# Adafruit_USB_Isolator.net
KiCad netlist of a schematic drawn in EAGLE
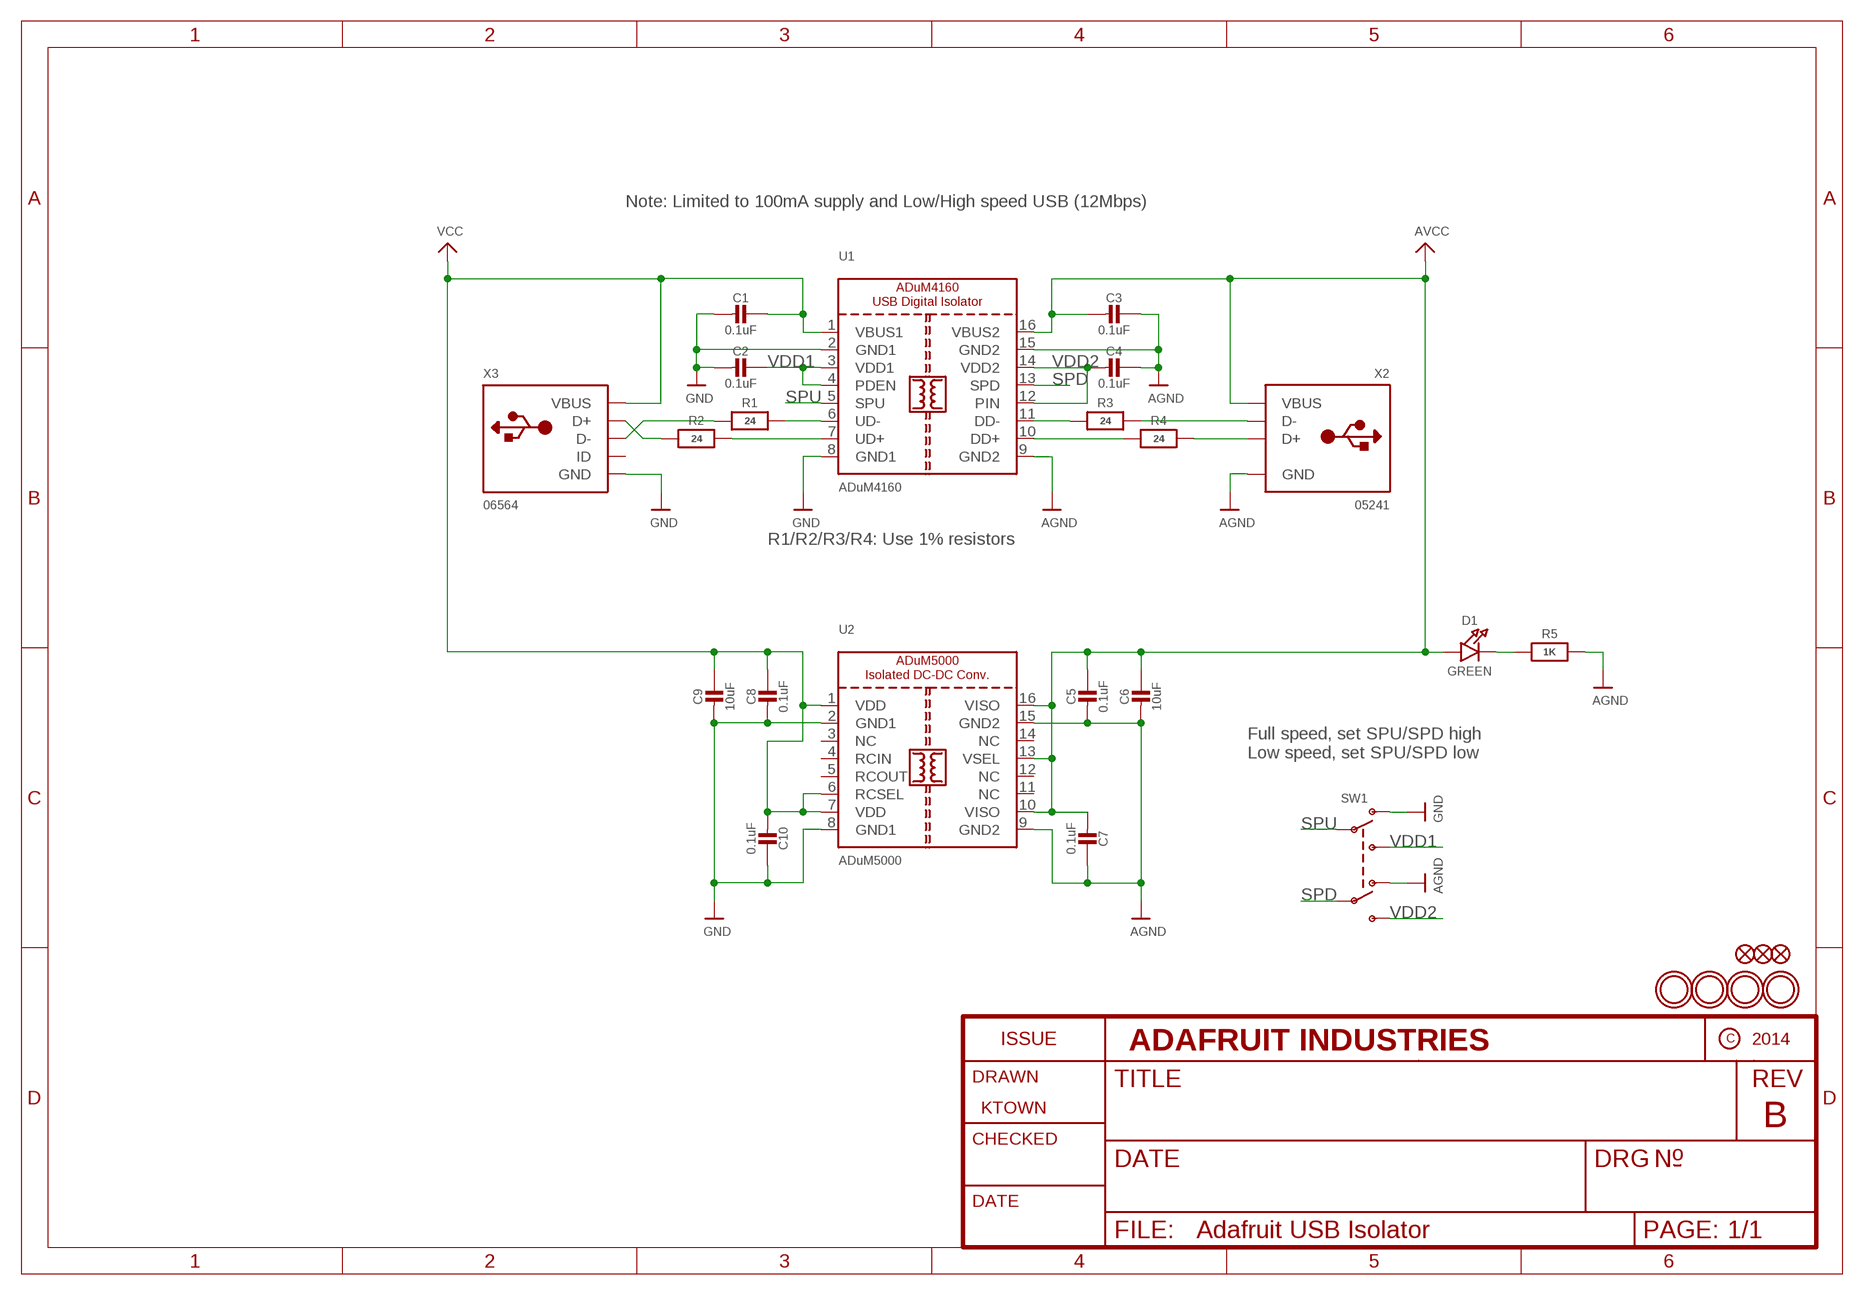
[diagram p0: schematic, sheet 1]

(export (version "E")
  (design (tool "Eeschema 10.0.6"))
  (components
    (comp (ref "C1")
      (value "0.1uF")
      (footprint "eagle-import:0805-NO")
      (libsource (lib "eagle-import") (part "CAP_CERAMIC0805-NOOUTLINE"))
    )
    (comp (ref "C2")
      (value "0.1uF")
      (footprint "eagle-import:0805-NO")
      (libsource (lib "eagle-import") (part "CAP_CERAMIC0805-NOOUTLINE"))
    )
    (comp (ref "C3")
      (value "0.1uF")
      (footprint "eagle-import:0805-NO")
      (libsource (lib "eagle-import") (part "CAP_CERAMIC0805-NOOUTLINE"))
    )
    (comp (ref "C4")
      (value "0.1uF")
      (footprint "eagle-import:0805-NO")
      (libsource (lib "eagle-import") (part "CAP_CERAMIC0805-NOOUTLINE"))
    )
    (comp (ref "C5")
      (value "0.1uF")
      (footprint "eagle-import:0805-NO")
      (libsource (lib "eagle-import") (part "CAP_CERAMIC0805-NOOUTLINE"))
    )
    (comp (ref "C6")
      (value "10uF")
      (footprint "eagle-import:0805-NO")
      (libsource (lib "eagle-import") (part "CAP_CERAMIC0805-NOOUTLINE"))
    )
    (comp (ref "C7")
      (value "0.1uF")
      (footprint "eagle-import:0805-NO")
      (libsource (lib "eagle-import") (part "CAP_CERAMIC0805-NOOUTLINE"))
    )
    (comp (ref "C8")
      (value "0.1uF")
      (footprint "eagle-import:0805-NO")
      (libsource (lib "eagle-import") (part "CAP_CERAMIC0805-NOOUTLINE"))
    )
    (comp (ref "C9")
      (value "10uF")
      (footprint "eagle-import:0805-NO")
      (libsource (lib "eagle-import") (part "CAP_CERAMIC0805-NOOUTLINE"))
    )
    (comp (ref "C10")
      (value "0.1uF")
      (footprint "eagle-import:0805-NO")
      (libsource (lib "eagle-import") (part "CAP_CERAMIC0805-NOOUTLINE"))
    )
    (comp (ref "D1")
      (value "GREEN")
      (footprint "eagle-import:CHIPLED_0805_NOOUTLINE")
      (libsource (lib "eagle-import") (part "LED0805_NOOUTLINE"))
    )
    (comp (ref "FID1")
      (value "FIDUCIAL\"\"")
      (footprint "eagle-import:FIDUCIAL_1MM")
      (libsource (lib "eagle-import") (part "FIDUCIAL{dblquote}{dblquote}"))
    )
    (comp (ref "FID2")
      (value "FIDUCIAL\"\"")
      (footprint "eagle-import:FIDUCIAL_1MM")
      (libsource (lib "eagle-import") (part "FIDUCIAL{dblquote}{dblquote}"))
    )
    (comp (ref "FID3")
      (value "FIDUCIAL\"\"")
      (footprint "eagle-import:FIDUCIAL_1MM")
      (libsource (lib "eagle-import") (part "FIDUCIAL{dblquote}{dblquote}"))
    )
    (comp (ref "R1")
      (value "24")
      (footprint "eagle-import:0805-NO")
      (libsource (lib "eagle-import") (part "RESISTOR0805_NOOUTLINE"))
    )
    (comp (ref "R2")
      (value "24")
      (footprint "eagle-import:0805-NO")
      (libsource (lib "eagle-import") (part "RESISTOR0805_NOOUTLINE"))
    )
    (comp (ref "R3")
      (value "24")
      (footprint "eagle-import:0805-NO")
      (libsource (lib "eagle-import") (part "RESISTOR0805_NOOUTLINE"))
    )
    (comp (ref "R4")
      (value "24")
      (footprint "eagle-import:_0805MP")
      (libsource (lib "eagle-import") (part "RESISTOR_0805MP"))
    )
    (comp (ref "R5")
      (value "1K")
      (footprint "eagle-import:0805-NO")
      (libsource (lib "eagle-import") (part "RESISTOR0805_NOOUTLINE"))
    )
    (comp (ref "SW1")
      (value "SWITCH_DPDTEG1390")
      (footprint "eagle-import:EG1390")
      (libsource (lib "eagle-import") (part "SWITCH_DPDTEG1390"))
    )
    (comp (ref "U$7")
      (value "MOUNTINGHOLE2.5_THICK")
      (footprint "eagle-import:MOUNTINGHOLE_2.5_PLATED_THICK")
      (libsource (lib "eagle-import") (part "MOUNTINGHOLE2.5_THICK"))
    )
    (comp (ref "U$8")
      (value "MOUNTINGHOLE2.5_THICK")
      (footprint "eagle-import:MOUNTINGHOLE_2.5_PLATED_THICK")
      (libsource (lib "eagle-import") (part "MOUNTINGHOLE2.5_THICK"))
    )
    (comp (ref "U$9")
      (value "MOUNTINGHOLE2.5_THICK")
      (footprint "eagle-import:MOUNTINGHOLE_2.5_PLATED_THICK")
      (libsource (lib "eagle-import") (part "MOUNTINGHOLE2.5_THICK"))
    )
    (comp (ref "U$10")
      (value "MOUNTINGHOLE2.5_THICK")
      (footprint "eagle-import:MOUNTINGHOLE_2.5_PLATED_THICK")
      (libsource (lib "eagle-import") (part "MOUNTINGHOLE2.5_THICK"))
    )
    (comp (ref "U1")
      (value "ADuM4160")
      (footprint "eagle-import:SOIC16WIDE")
      (libsource (lib "eagle-import") (part "ADUM4160"))
    )
    (comp (ref "U2")
      (value "ADuM5000")
      (footprint "eagle-import:SOIC16WIDE")
      (libsource (lib "eagle-import") (part "ADUM5000"))
    )
    (comp (ref "X2")
      (value "05241")
      (footprint "eagle-import:USB_HOST-PTH")
      (libsource (lib "eagle-import") (part "USB_TYPEAPTHFML"))
    )
    (comp (ref "X3")
      (value "06564")
      (footprint "eagle-import:USB-MINIB_LARGER")
      (libsource (lib "eagle-import") (part "USBMINIBLARGE"))
    )
  )
  (nets
    (net (code "1") (name "/SPD") (class "Default")
      (node (ref "SW1") (pin "P2") (pinfunction "P2_P2") (pintype "passive"))
      (node (ref "U1") (pin "13") (pinfunction "SPD_13") (pintype "input"))
    )
    (net (code "2") (name "/SPU") (class "Default")
      (node (ref "SW1") (pin "P1") (pinfunction "P1_P1") (pintype "passive"))
      (node (ref "U1") (pin "5") (pinfunction "SPU_5") (pintype "input"))
    )
    (net (code "3") (name "/VDD1") (class "Default")
      (node (ref "C2") (pin "1") (pinfunction "1_1") (pintype "passive"))
      (node (ref "SW1") (pin "S1") (pinfunction "S1_S1") (pintype "passive"))
      (node (ref "U1") (pin "3") (pinfunction "VDD1_3") (pintype "power_in"))
      (node (ref "U1") (pin "4") (pinfunction "PDEN_4") (pintype "input"))
    )
    (net (code "4") (name "/VDD2") (class "Default")
      (node (ref "C4") (pin "2") (pinfunction "2_2") (pintype "passive"))
      (node (ref "SW1") (pin "S2") (pinfunction "S2_S2") (pintype "passive"))
      (node (ref "U1") (pin "12") (pinfunction "PIN_12") (pintype "input"))
      (node (ref "U1") (pin "14") (pinfunction "VDD2_14") (pintype "power_in"))
    )
    (net (code "5") (name "AGND") (class "Default")
      (node (ref "C3") (pin "1") (pinfunction "1_1") (pintype "passive"))
      (node (ref "C4") (pin "1") (pinfunction "1_1") (pintype "passive"))
      (node (ref "C5") (pin "2") (pinfunction "2_2") (pintype "passive"))
      (node (ref "C6") (pin "2") (pinfunction "2_2") (pintype "passive"))
      (node (ref "C7") (pin "1") (pinfunction "1_1") (pintype "passive"))
      (node (ref "R5") (pin "2") (pinfunction "2_2") (pintype "passive"))
      (node (ref "SW1") (pin "O2") (pinfunction "O2_O2") (pintype "passive"))
      (node (ref "U1") (pin "15") (pinfunction "GND2_15") (pintype "power_in"))
      (node (ref "U1") (pin "9") (pinfunction "GND2_9") (pintype "power_in"))
      (node (ref "U2") (pin "15") (pinfunction "GND2_15") (pintype "power_in"))
      (node (ref "U2") (pin "9") (pinfunction "GND2_9") (pintype "power_in"))
      (node (ref "X2") (pin "GND") (pinfunction "GND_GND") (pintype "power_in"))
    )
    (net (code "6") (name "AVCC") (class "Default")
      (node (ref "C3") (pin "2") (pinfunction "2_2") (pintype "passive"))
      (node (ref "C5") (pin "1") (pinfunction "1_1") (pintype "passive"))
      (node (ref "C6") (pin "1") (pinfunction "1_1") (pintype "passive"))
      (node (ref "C7") (pin "2") (pinfunction "2_2") (pintype "passive"))
      (node (ref "D1") (pin "A") (pinfunction "A_A") (pintype "passive"))
      (node (ref "U1") (pin "16") (pinfunction "VBUS2_16") (pintype "power_in"))
      (node (ref "U2") (pin "10") (pinfunction "VISO_10") (pintype "bidirectional"))
      (node (ref "U2") (pin "13") (pinfunction "VSEL_13") (pintype "input"))
      (node (ref "U2") (pin "16") (pinfunction "VISO_16") (pintype "power_in"))
      (node (ref "X2") (pin "VBUS") (pinfunction "VBUS_VBUS") (pintype "power_in"))
    )
    (net (code "7") (name "GND") (class "Default")
      (node (ref "C1") (pin "2") (pinfunction "2_2") (pintype "passive"))
      (node (ref "C10") (pin "1") (pinfunction "1_1") (pintype "passive"))
      (node (ref "C2") (pin "2") (pinfunction "2_2") (pintype "passive"))
      (node (ref "C8") (pin "2") (pinfunction "2_2") (pintype "passive"))
      (node (ref "C9") (pin "2") (pinfunction "2_2") (pintype "passive"))
      (node (ref "SW1") (pin "O1") (pinfunction "O1_O1") (pintype "passive"))
      (node (ref "U1") (pin "2") (pinfunction "GND1_2") (pintype "power_in"))
      (node (ref "U1") (pin "8") (pinfunction "GND1_8") (pintype "power_in"))
      (node (ref "U2") (pin "2") (pinfunction "GND1_2") (pintype "power_in"))
      (node (ref "U2") (pin "8") (pinfunction "GND1_8") (pintype "power_in"))
      (node (ref "X3") (pin "GND") (pinfunction "GND_GND") (pintype "power_in"))
      (node (ref "X3") (pin "GND1") (pinfunction "GND_GND1") (pintype "power_in"))
      (node (ref "X3") (pin "GND2") (pinfunction "GND_GND2") (pintype "power_in"))
      (node (ref "X3") (pin "GND3") (pinfunction "GND_GND3") (pintype "power_in"))
      (node (ref "X3") (pin "GND4") (pinfunction "GND_GND4") (pintype "power_in"))
    )
    (net (code "8") (name "Net-(D1-PadC)") (class "Default")
      (node (ref "D1") (pin "C") (pinfunction "C_C") (pintype "passive"))
      (node (ref "R5") (pin "1") (pinfunction "1_1") (pintype "passive"))
    )
    (net (code "9") (name "Net-(R1-Pad1)") (class "Default")
      (node (ref "R1") (pin "1") (pinfunction "1_1") (pintype "passive"))
      (node (ref "X3") (pin "D-") (pinfunction "D-_D-") (pintype "bidirectional"))
    )
    (net (code "10") (name "Net-(R2-Pad1)") (class "Default")
      (node (ref "R2") (pin "1") (pinfunction "1_1") (pintype "passive"))
      (node (ref "X3") (pin "D+") (pinfunction "D+_D+") (pintype "bidirectional"))
    )
    (net (code "11") (name "Net-(R3-Pad2)") (class "Default")
      (node (ref "R3") (pin "2") (pinfunction "2_2") (pintype "passive"))
      (node (ref "X2") (pin "D-") (pinfunction "D-_D-") (pintype "bidirectional"))
    )
    (net (code "12") (name "Net-(R4-Pad2)") (class "Default")
      (node (ref "R4") (pin "2") (pinfunction "2_2") (pintype "passive"))
      (node (ref "X2") (pin "D+") (pinfunction "D+_D+") (pintype "bidirectional"))
    )
    (net (code "13") (name "Net-(U1-DD+)") (class "Default")
      (node (ref "R4") (pin "1") (pinfunction "1_1") (pintype "passive"))
      (node (ref "U1") (pin "10") (pinfunction "DD+_10") (pintype "bidirectional"))
    )
    (net (code "14") (name "Net-(U1-DD-)") (class "Default")
      (node (ref "R3") (pin "1") (pinfunction "1_1") (pintype "passive"))
      (node (ref "U1") (pin "11") (pinfunction "DD-_11") (pintype "bidirectional"))
    )
    (net (code "15") (name "Net-(U1-UD+)") (class "Default")
      (node (ref "R2") (pin "2") (pinfunction "2_2") (pintype "passive"))
      (node (ref "U1") (pin "7") (pinfunction "UD+_7") (pintype "bidirectional"))
    )
    (net (code "16") (name "Net-(U1-UD-)") (class "Default")
      (node (ref "R1") (pin "2") (pinfunction "2_2") (pintype "passive"))
      (node (ref "U1") (pin "6") (pinfunction "UD-_6") (pintype "bidirectional"))
    )
    (net (code "17") (name "VCC") (class "Default")
      (node (ref "C1") (pin "1") (pinfunction "1_1") (pintype "passive"))
      (node (ref "C10") (pin "2") (pinfunction "2_2") (pintype "passive"))
      (node (ref "C8") (pin "1") (pinfunction "1_1") (pintype "passive"))
      (node (ref "C9") (pin "1") (pinfunction "1_1") (pintype "passive"))
      (node (ref "U1") (pin "1") (pinfunction "VBUS1_1") (pintype "power_in"))
      (node (ref "U2") (pin "1") (pinfunction "VDD_1") (pintype "power_in"))
      (node (ref "U2") (pin "6") (pinfunction "RCSEL_6") (pintype "input"))
      (node (ref "U2") (pin "7") (pinfunction "VDD_7") (pintype "bidirectional"))
      (node (ref "X3") (pin "VBUS") (pinfunction "VBUS_VBUS") (pintype "power_in"))
    )
    (net (code "18") (name "unconnected-(U2-NC-Pad3)") (class "Default")
      (node (ref "U2") (pin "3") (pinfunction "NC_3") (pintype "no_connect"))
    )
    (net (code "19") (name "unconnected-(U2-NC-Pad11)") (class "Default")
      (node (ref "U2") (pin "11") (pinfunction "NC_11") (pintype "no_connect"))
    )
    (net (code "20") (name "unconnected-(U2-NC-Pad12)") (class "Default")
      (node (ref "U2") (pin "12") (pinfunction "NC_12") (pintype "no_connect"))
    )
    (net (code "21") (name "unconnected-(U2-NC-Pad14)") (class "Default")
      (node (ref "U2") (pin "14") (pinfunction "NC_14") (pintype "no_connect"))
    )
    (net (code "22") (name "unconnected-(U2-RCIN-Pad4)") (class "Default")
      (node (ref "U2") (pin "4") (pinfunction "RCIN_4") (pintype "input"))
    )
    (net (code "23") (name "unconnected-(U2-RCOUT-Pad5)") (class "Default")
      (node (ref "U2") (pin "5") (pinfunction "RCOUT_5") (pintype "output"))
    )
    (net (code "24") (name "unconnected-(X3-PadID)") (class "Default")
      (node (ref "X3") (pin "ID") (pinfunction "ID_ID") (pintype "bidirectional"))
    )
  )
)
